# H05R0.net
KiCad netlist of a schematic drawn in EAGLE
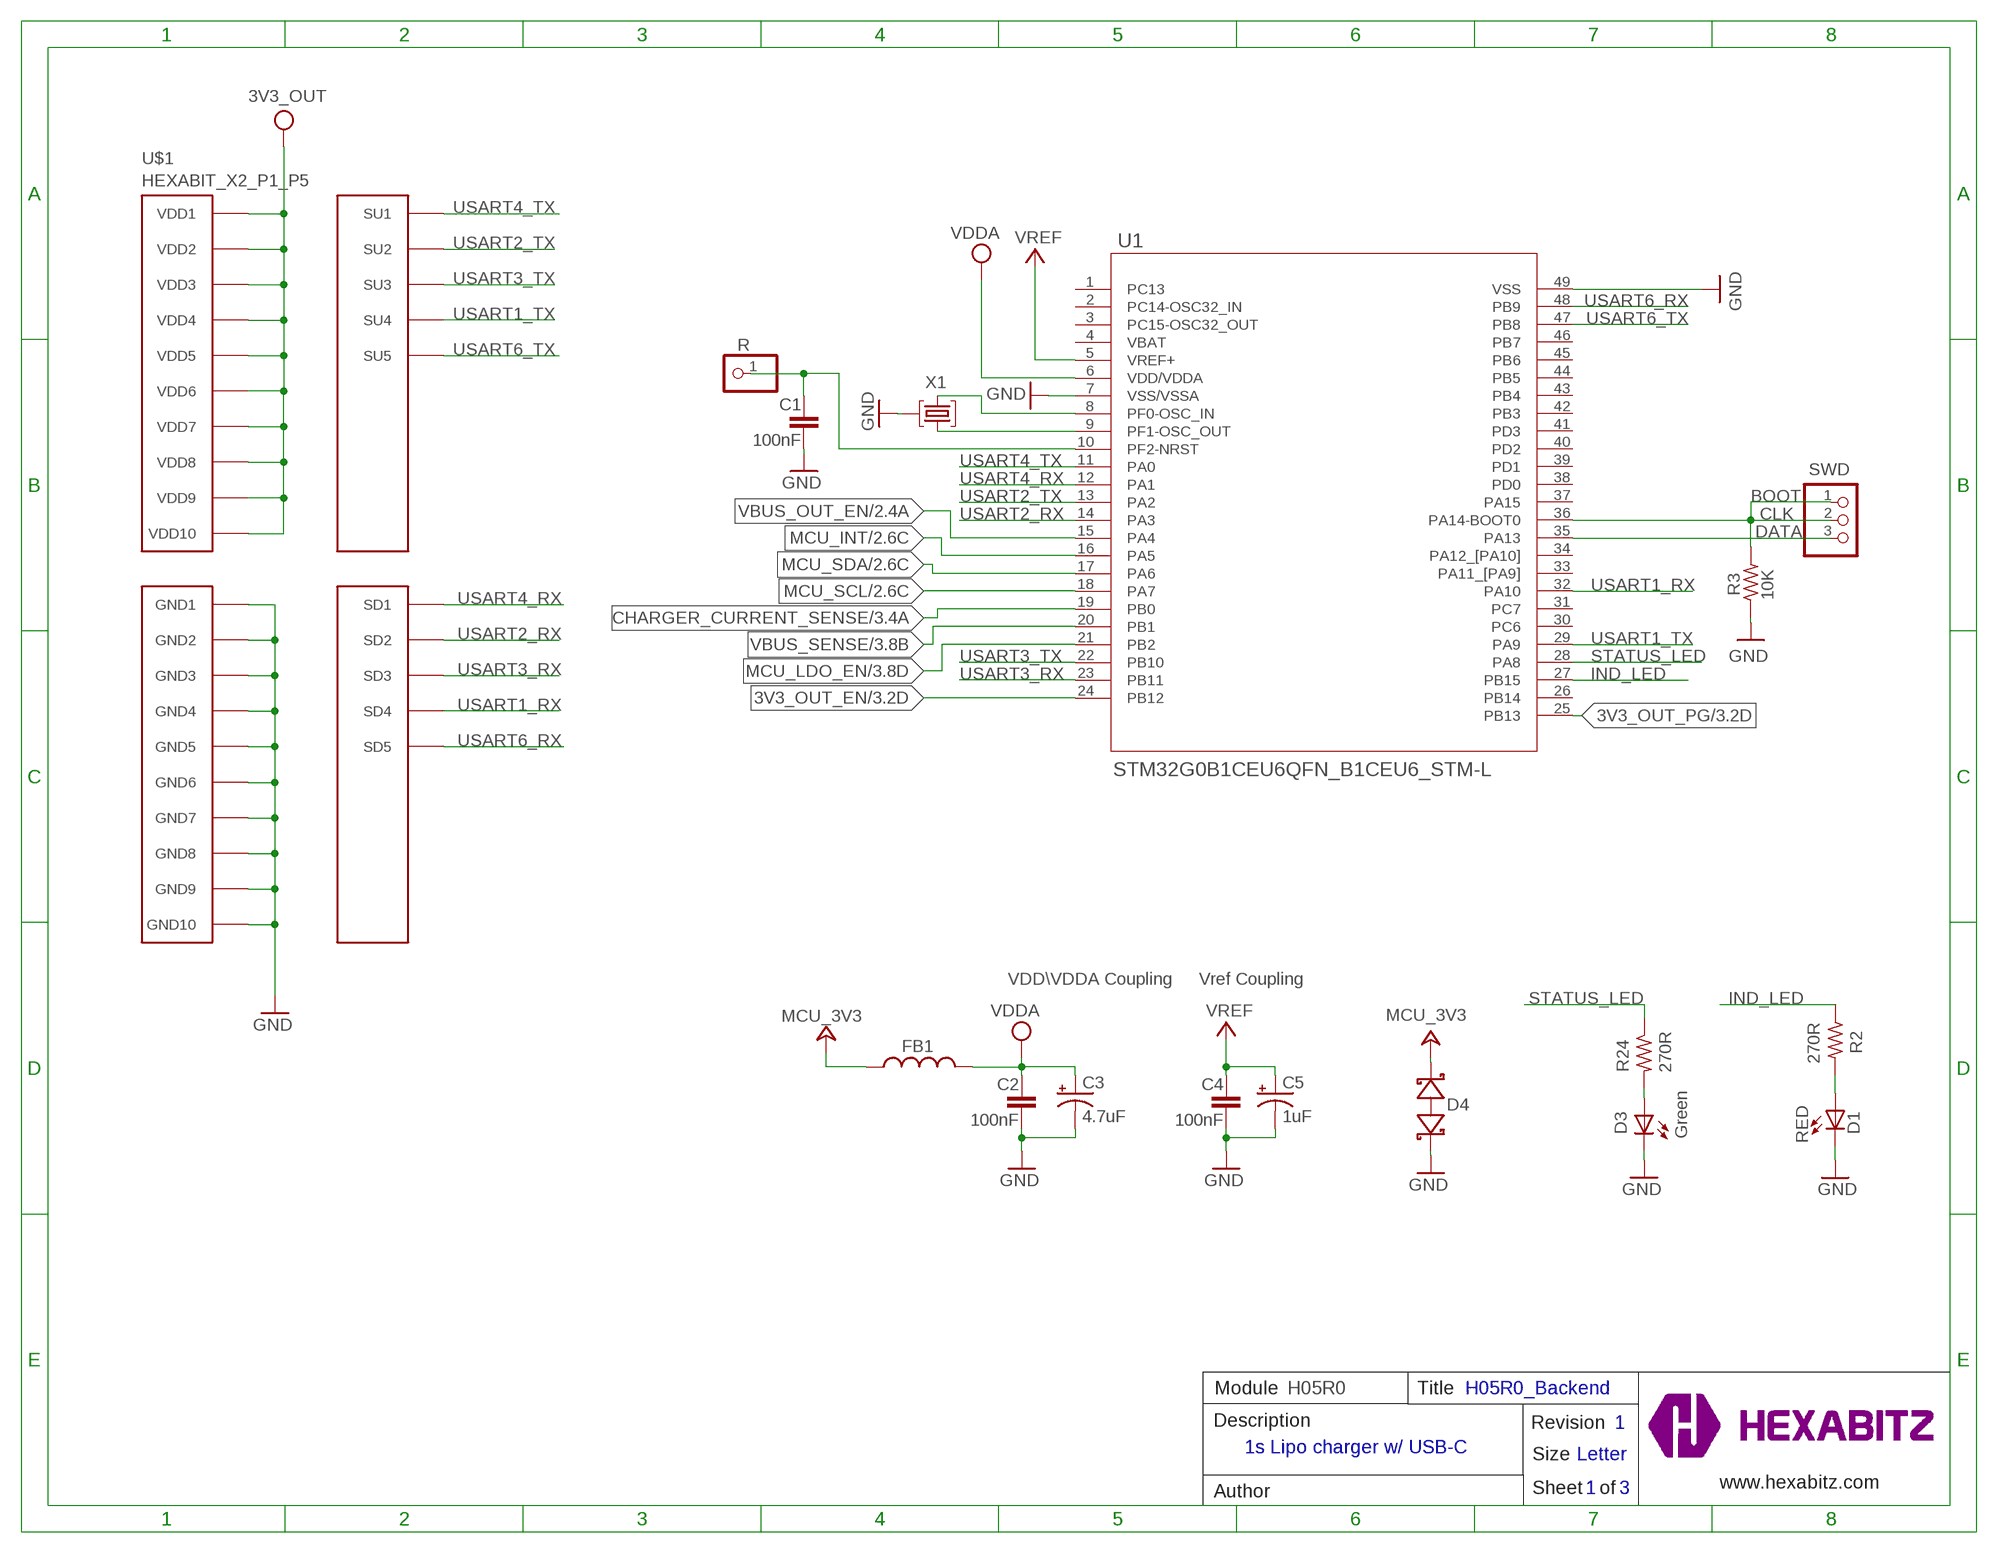
[diagram p0: schematic, sheet 1]
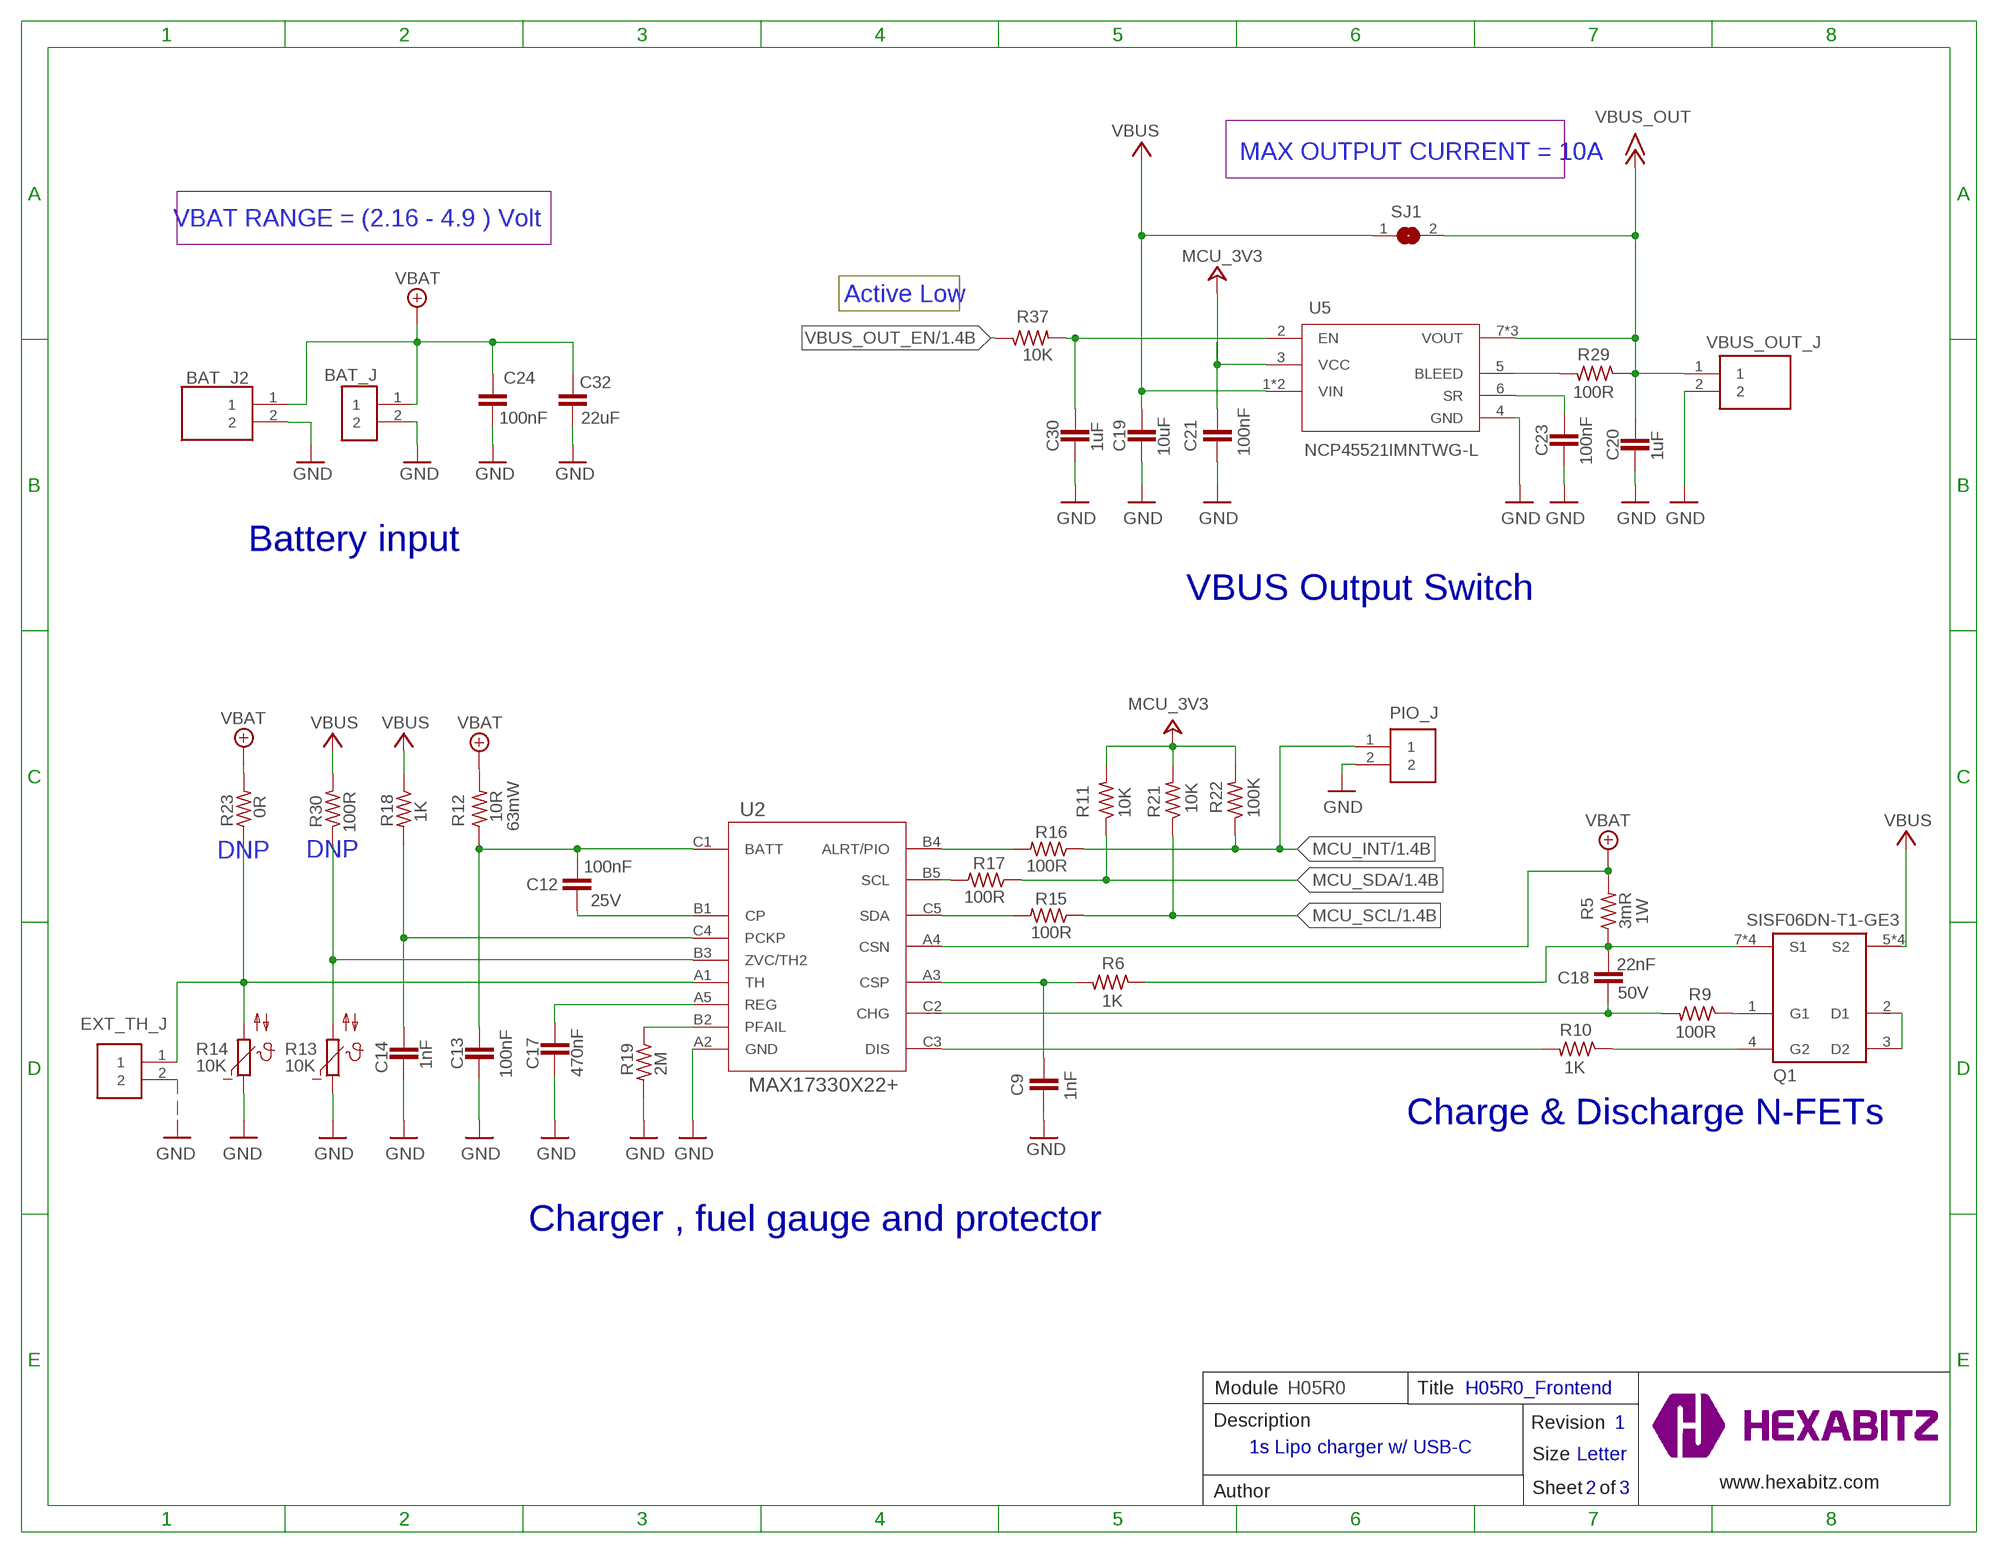
[diagram p1: schematic, sheet 2]
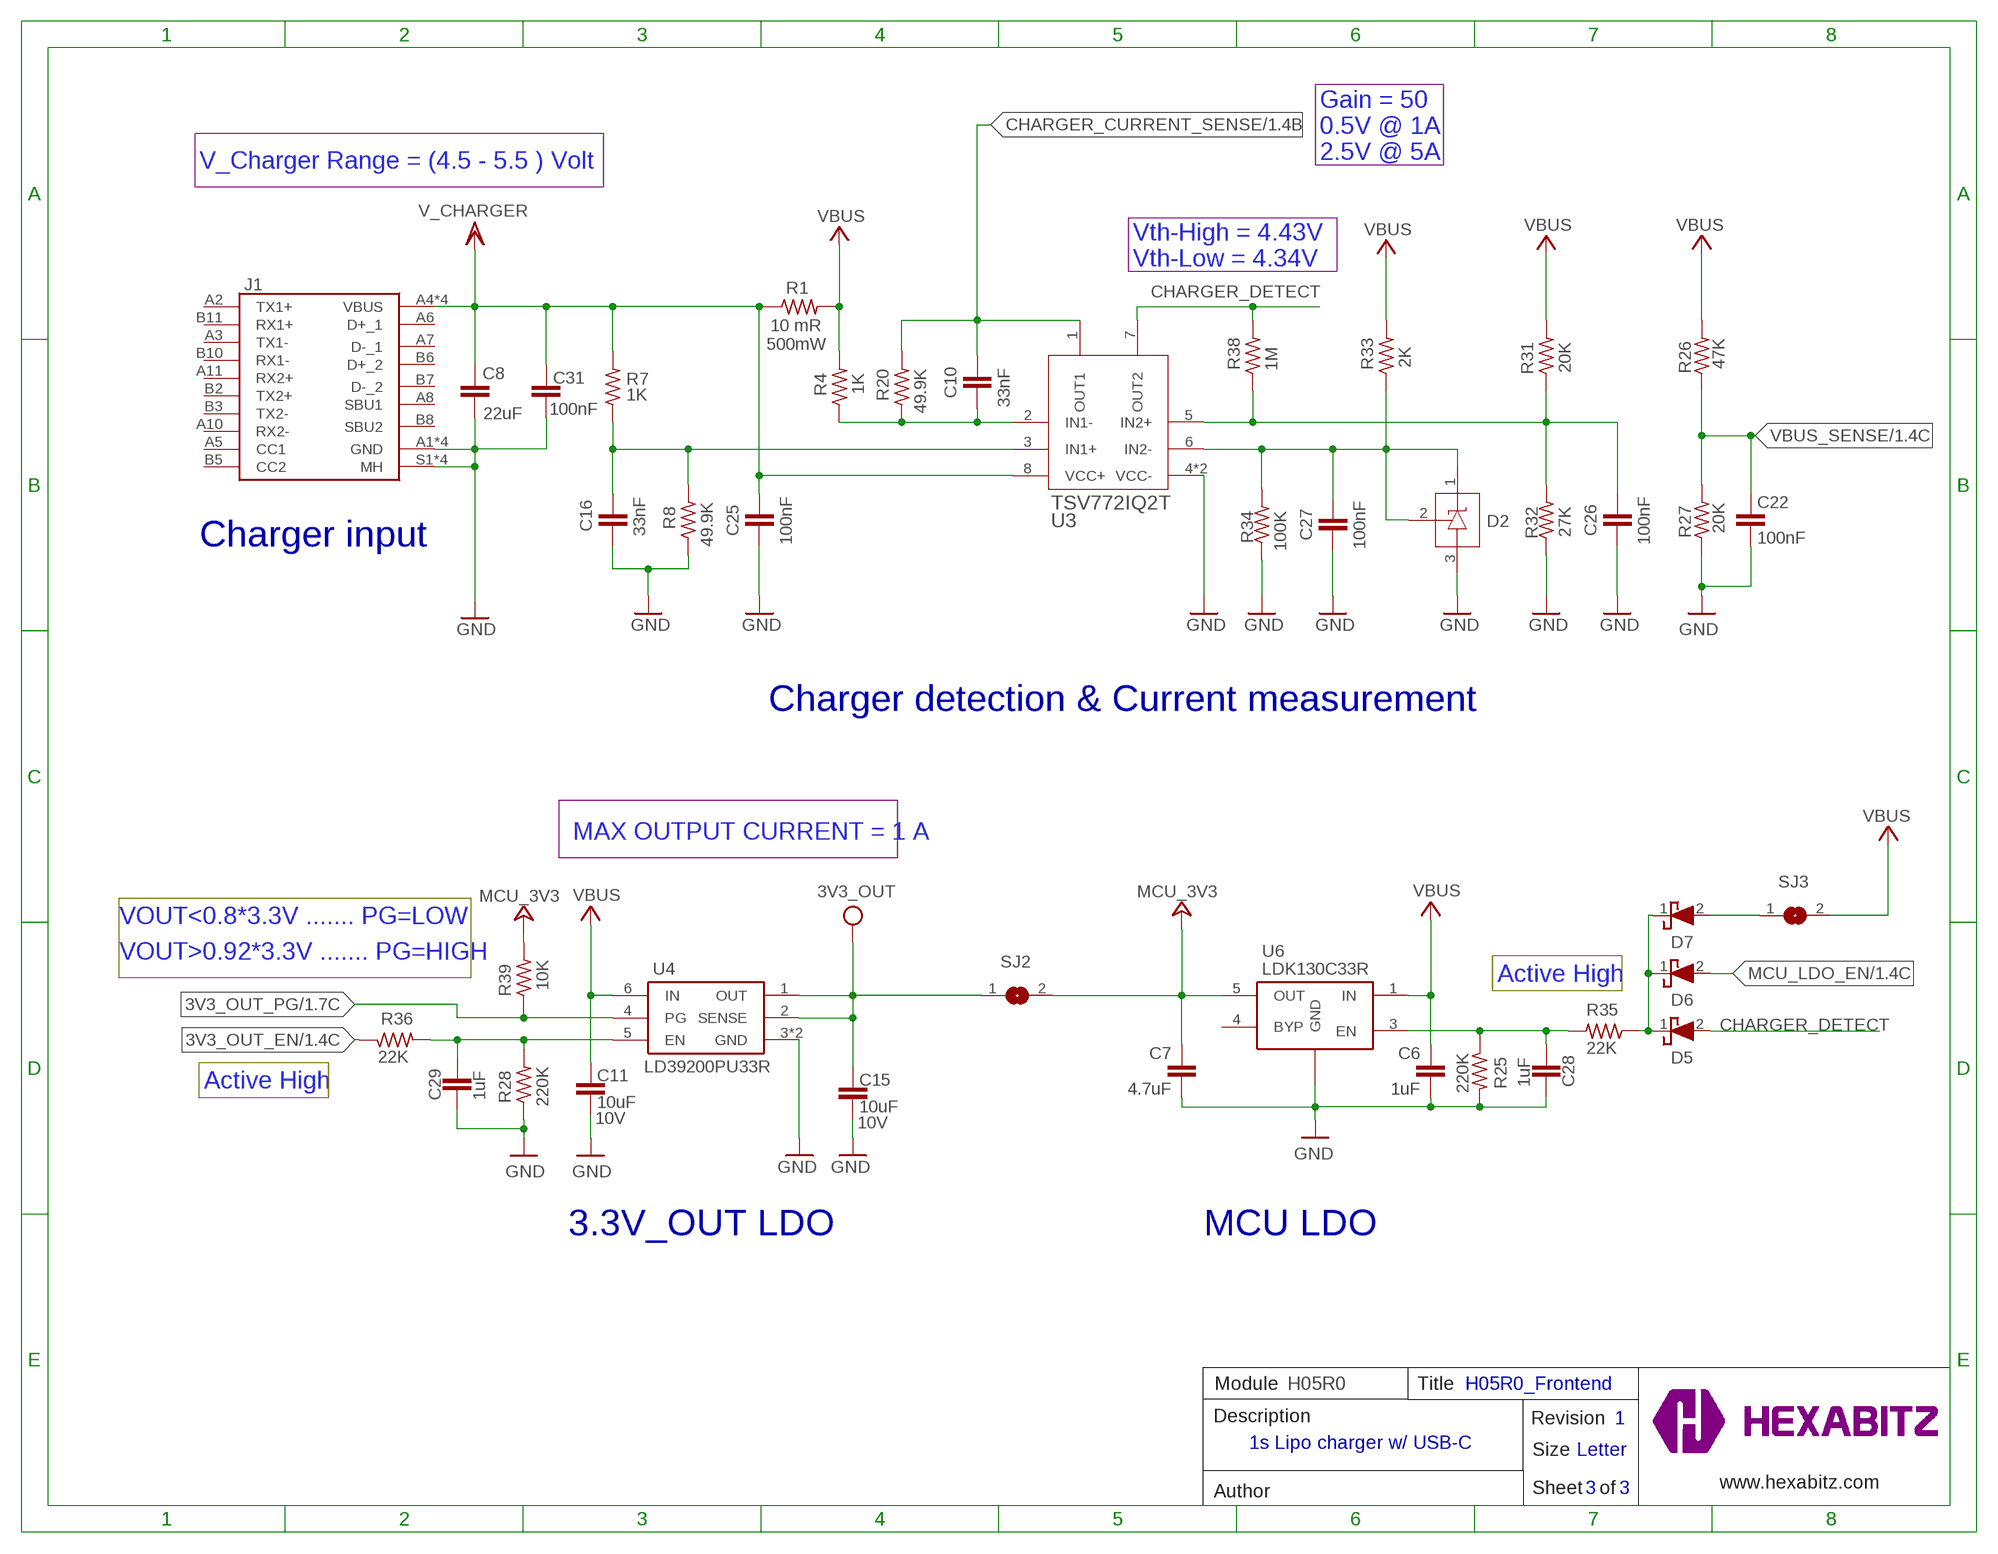
[diagram p2: schematic, sheet 3]

(export (version "E")
  (design (tool "Eeschema 10.0.6"))
  (components
    (comp (ref "C1")
      (value "100nF")
      (footprint "eagle-import:C-0603")
      (libsource (lib "eagle-import") (part "C-0603"))
    )
    (comp (ref "C2")
      (value "100nF")
      (footprint "eagle-import:C-0603")
      (libsource (lib "eagle-import") (part "C-0603"))
    )
    (comp (ref "C3")
      (value "4.7uF")
      (footprint "eagle-import:C-0805-POL")
      (libsource (lib "eagle-import") (part "C-0805-POL"))
    )
    (comp (ref "C4")
      (value "100nF")
      (footprint "eagle-import:C-0603")
      (libsource (lib "eagle-import") (part "C-0603"))
    )
    (comp (ref "C5")
      (value "1uF")
      (footprint "eagle-import:C-0805-POL")
      (libsource (lib "eagle-import") (part "C-0805-POL"))
    )
    (comp (ref "D1")
      (value "RED")
      (footprint "eagle-import:VLMS1300-GS08")
      (fields
        (field (name "MPN") "VLMS1300-GS08")
        (field (name "MFN") "Vishay")
        (field (name "MPN_1") "VLMS1300-GS08")
        (field (name "OCTOPART_URL") "https://octopart.com/vlms1300-gs08-vishay-21709201?r=sp&s=_gcP4_q8T1SC6PJQPTQ9yA")
      )
      (libsource (lib "eagle-import") (part "VLMS1300-GS08"))
    )
    (comp (ref "D3")
      (value "Green")
      (footprint "eagle-import:VLMTG1300-GS08")
      (fields
        (field (name "MPN") "VLMTG1300-GS08")
        (field (name "MFN") "Vishay")
        (field (name "MPN_1") "VLMS1300-GS08")
        (field (name "OCTOPART_URL") "https://octopart.com/vlms1300-gs08-vishay-21709201?r=sp&s=_gcP4_q8T1SC6PJQPTQ9yA")
      )
      (libsource (lib "eagle-import") (part "VLMTG1300-GS08"))
    )
    (comp (ref "D4")
      (value "BOURNS_CDSOD323-T03SCBOURNS_CDSOD323-T03SC_0_0")
      (footprint "eagle-import:BOURNS_CDSOD323-T03SC_0")
      (fields (field (name "MPN") "CDSOD323-T03SC"))
      (libsource (lib "eagle-import") (part "BOURNS_CDSOD323-T03SCBOURNS_CDSOD323-T03SC_0_0"))
    )
    (comp (ref "FB1")
      (value "FB-0603")
      (footprint "eagle-import:FB-0603")
      (libsource (lib "eagle-import") (part "FB-0603"))
    )
    (comp (ref "R")
      (value "R")
      (footprint "eagle-import:1X01")
      (fields (field (name "MPN") "87227-1"))
      (libsource (lib "eagle-import") (part "PINHD-1X1"))
    )
    (comp (ref "R2")
      (value "270R")
      (footprint "eagle-import:R-0603")
      (libsource (lib "eagle-import") (part "R-0603"))
    )
    (comp (ref "R3")
      (value "10K")
      (footprint "eagle-import:R-0603")
      (libsource (lib "eagle-import") (part "R-0603"))
    )
    (comp (ref "R24")
      (value "270R")
      (footprint "eagle-import:R-0603")
      (libsource (lib "eagle-import") (part "R-0603"))
    )
    (comp (ref "SWD")
      (value "PINHD-1X3")
      (footprint "eagle-import:1X03")
      (libsource (lib "eagle-import") (part "PINHD-1X3"))
    )
    (comp (ref "TRIMBLE-LOGO1")
      (value "HEXA-LOGO")
      (footprint "eagle-import:HEXA-LOGO")
      (libsource (lib "eagle-import") (part "HEXA-LOGO"))
    )
    (comp (ref "U$1")
      (value "HEXABIT_X2_P1_P5")
      (footprint "eagle-import:HEXABIT_17.32_X2_P1_P5")
      (libsource (lib "eagle-import") (part "HEXABIT_X2_P1_P5"))
    )
    (comp (ref "U1")
      (value "STM32G0B1CEU6QFN_B1CEU6_STM-L")
      (footprint "eagle-import:QFN_B1CEU6_STM-L")
      (fields
        (field (name "MANUFACTURER_PART_NUMBER") "STM32G0B1CEU6")
        (field (name "COPYRIGHT") "Copyright (C) 2021 Ultra Librarian. All rights reserved.")
      )
      (libsource (lib "eagle-import") (part "STM32G0B1CEU6QFN_B1CEU6_STM-L"))
    )
    (comp (ref "X1")
      (value "XTALL_CSTCE8M00G52")
      (footprint "eagle-import:XTALL_CSTCE8M00G52")
      (fields (field (name "MPN") "CSTCE8M00G52Z-R0"))
      (libsource (lib "eagle-import") (part "XTALL_CSTCE8M00G52"))
    )
    (comp (ref "BAT_J")
      (value "B2B-PH-K-S(LF)(SN)")
      (footprint "eagle-import:JST_B2B-PH-K-S(LF)(SN)")
      (fields (field (name "MF") "JST Sales"))
      (libsource (lib "eagle-import") (part "B2B-PH-K-S(LF)(SN)"))
    )
    (comp (ref "BAT_J2")
      (value "B2P-VH-FB-B_LF__SN_")
      (footprint "eagle-import:B2PVHFBBLFSN")
      (fields (field (name "MANUFACTURER_PART_NUMBER") "B2P-VH-FB-B(LF)(SN)"))
      (libsource (lib "eagle-import") (part "B2P-VH-FB-B_LF__SN_"))
    )
    (comp (ref "C9")
      (value "1nF")
      (footprint "eagle-import:C-0603")
      (fields (field (name "VOLTAGE_RATING") "50V"))
      (libsource (lib "eagle-import") (part "C-0603"))
    )
    (comp (ref "C12")
      (value "100nF")
      (footprint "eagle-import:C-0603")
      (fields (field (name "VOLTAGE_RATING") "25V"))
      (libsource (lib "eagle-import") (part "C-0603"))
    )
    (comp (ref "C13")
      (value "100nF")
      (footprint "eagle-import:C-0603")
      (fields (field (name "VOLTAGE_RATING") "10V"))
      (libsource (lib "eagle-import") (part "C-0603"))
    )
    (comp (ref "C14")
      (value "1nF")
      (footprint "eagle-import:C-0603")
      (fields (field (name "VOLTAGE_RATING") "50V"))
      (libsource (lib "eagle-import") (part "C-0603"))
    )
    (comp (ref "C17")
      (value "470nF")
      (footprint "eagle-import:C-0603")
      (fields (field (name "VOLTAGE_RATING") "10V"))
      (libsource (lib "eagle-import") (part "C-0603"))
    )
    (comp (ref "C18")
      (value "22nF")
      (footprint "eagle-import:C-0603")
      (fields (field (name "VOLTAGE_RATING") "50V"))
      (libsource (lib "eagle-import") (part "C-0603"))
    )
    (comp (ref "C19")
      (value "10uF")
      (footprint "eagle-import:C-0805")
      (libsource (lib "eagle-import") (part "C-0805"))
    )
    (comp (ref "C20")
      (value "1uF")
      (footprint "eagle-import:C-0805")
      (libsource (lib "eagle-import") (part "C-0805"))
    )
    (comp (ref "C21")
      (value "100nF")
      (footprint "eagle-import:C-0603")
      (fields (field (name "MPN") "GRM187R61A226ME15") (field (name "VOLTAGE_RATING") "10V"))
      (libsource (lib "eagle-import") (part "C-0603"))
    )
    (comp (ref "C23")
      (value "100nF")
      (footprint "eagle-import:C-0603")
      (fields (field (name "MPN") "GRM187R61A226ME15") (field (name "VOLTAGE_RATING") "10V"))
      (libsource (lib "eagle-import") (part "C-0603"))
    )
    (comp (ref "C24")
      (value "100nF")
      (footprint "eagle-import:C-0603")
      (fields (field (name "VOLTAGE_RATING") "50V"))
      (libsource (lib "eagle-import") (part "C-0603"))
    )
    (comp (ref "C30")
      (value "1uF")
      (footprint "eagle-import:C-0805")
      (fields (field (name "MPN") "GRM187R61A226ME15") (field (name "VOLTAGE_RATING") "10V"))
      (libsource (lib "eagle-import") (part "C-0805"))
    )
    (comp (ref "C32")
      (value "22uF")
      (footprint "eagle-import:C-0805")
      (libsource (lib "eagle-import") (part "C-0805"))
    )
    (comp (ref "EXT_TH_J")
      (value "3-644456-2")
      (footprint "eagle-import:TE_3-644456-2")
      (fields (field (name "MF") "TE Connectivity") (field (name "MPN") "87224-1"))
      (libsource (lib "eagle-import") (part "3-644456-2"))
    )
    (comp (ref "PIO_J")
      (value "3-644456-2")
      (footprint "eagle-import:TE_3-644456-2")
      (fields (field (name "MF") "TE Connectivity") (field (name "MPN") "87224-1"))
      (libsource (lib "eagle-import") (part "3-644456-2"))
    )
    (comp (ref "Q1")
      (value "SISF06DN-T1-GE3")
      (footprint "eagle-import:SISF06DNT1GE3")
      (fields (field (name "MOUSER_PART_NUMBER") "78-SISF06DN-T1-GE3"))
      (libsource (lib "eagle-import") (part "SISF06DN-T1-GE3"))
    )
    (comp (ref "R5")
      (value "3mR")
      (footprint "eagle-import:R1206")
      (fields
        (field (name "MPN") "RNCF2512BTE1M10")
        (field (name "MPN_1") "WFC12063L000FE66")
        (field (name "OCTOPART_URL") "https://www.digikey.com/en/products/detail/vishay-dale/WFC12063L000FE66/15908406")
        (field (name "POWER") "1W")
      )
      (libsource (lib "eagle-import") (part "R_1206R1206"))
    )
    (comp (ref "R6")
      (value "1K")
      (footprint "eagle-import:R-0603")
      (libsource (lib "eagle-import") (part "R-0603"))
    )
    (comp (ref "R9")
      (value "100R")
      (footprint "eagle-import:R-0603")
      (libsource (lib "eagle-import") (part "R-0603"))
    )
    (comp (ref "R10")
      (value "1K")
      (footprint "eagle-import:R-0603")
      (libsource (lib "eagle-import") (part "R-0603"))
    )
    (comp (ref "R11")
      (value "10K")
      (footprint "eagle-import:R-0603")
      (libsource (lib "eagle-import") (part "R-0603"))
    )
    (comp (ref "R12")
      (value "10R")
      (footprint "eagle-import:R-0603")
      (fields (field (name "POWER") "63mW"))
      (libsource (lib "eagle-import") (part "R-0603"))
    )
    (comp (ref "R13")
      (value "10K")
      (footprint "eagle-import:R-0603")
      (fields (field (name "MPN") "NCP18XH103F03RB"))
      (libsource (lib "eagle-import") (part "NCP18XH103F03RBNCP18XH103F03RB"))
    )
    (comp (ref "R14")
      (value "10K")
      (footprint "eagle-import:R-0603")
      (fields (field (name "MPN") "NCP18XH103F03RB"))
      (libsource (lib "eagle-import") (part "NCP18XH103F03RBNCP18XH103F03RB"))
    )
    (comp (ref "R15")
      (value "100R")
      (footprint "eagle-import:R-0603")
      (libsource (lib "eagle-import") (part "R-0603"))
    )
    (comp (ref "R16")
      (value "100R")
      (footprint "eagle-import:R-0603")
      (libsource (lib "eagle-import") (part "R-0603"))
    )
    (comp (ref "R17")
      (value "100R")
      (footprint "eagle-import:R-0603")
      (libsource (lib "eagle-import") (part "R-0603"))
    )
    (comp (ref "R18")
      (value "1K")
      (footprint "eagle-import:R-0603")
      (libsource (lib "eagle-import") (part "R-0603"))
    )
    (comp (ref "R19")
      (value "2M")
      (footprint "eagle-import:R-0603")
      (libsource (lib "eagle-import") (part "R-0603"))
    )
    (comp (ref "R21")
      (value "10K")
      (footprint "eagle-import:R-0603")
      (libsource (lib "eagle-import") (part "R-0603"))
    )
    (comp (ref "R22")
      (value "100K")
      (footprint "eagle-import:R-0603")
      (libsource (lib "eagle-import") (part "R-0603"))
    )
    (comp (ref "R23")
      (value "DNP")
      (footprint "eagle-import:R-0603")
      (fields (field (name "RESISTANCE") "0R") (field (name "STATE") "DNP"))
      (libsource (lib "eagle-import") (part "R-0603"))
    )
    (comp (ref "R29")
      (value "100R")
      (footprint "eagle-import:R-0603")
      (libsource (lib "eagle-import") (part "R-0603"))
    )
    (comp (ref "R30")
      (value "100R")
      (footprint "eagle-import:R-0603")
      (fields (field (name "STATE") "DNP"))
      (libsource (lib "eagle-import") (part "R-0603"))
    )
    (comp (ref "R37")
      (value "10K")
      (footprint "eagle-import:R-0603")
      (libsource (lib "eagle-import") (part "R-0603"))
    )
    (comp (ref "SJ1") (value "SJ") (footprint "eagle-import:SJ") (libsource (lib "eagle-import") (part "SJ")))
    (comp (ref "U2")
      (value "MAX17330X22+")
      (footprint "eagle-import:21-100433_W151J2+1_MXM")
      (fields (field (name "COPYRIGHT") "Copyright (C) 2023 Ultra Librarian. All rights reserved."))
      (libsource (lib "eagle-import") (part "MAX17330X22+21-100433_W151J2+1_MXM"))
    )
    (comp (ref "U5")
      (value "NCP45521IMNTWG-L")
      (footprint "eagle-import:DFN8_2X2_ONS")
      (fields (field (name "COPYRIGHT") "Copyright (C) 2024 Ultra Librarian. All rights reserved."))
      (libsource (lib "eagle-import") (part "NCP45521IMNTWG-LDFN8_2X2_ONS"))
    )
    (comp (ref "VBUS_OUT_J")
      (value "1984617")
      (footprint "eagle-import:1984617")
      (fields (field (name "MOUSER_PART_NUMBER") "651-1984617"))
      (libsource (lib "eagle-import") (part "1984617"))
    )
    (comp (ref "C6")
      (value "1uF")
      (footprint "eagle-import:C-0805")
      (libsource (lib "eagle-import") (part "C-0805"))
    )
    (comp (ref "C7")
      (value "4.7uF")
      (footprint "eagle-import:C-0805")
      (libsource (lib "eagle-import") (part "C-0805"))
    )
    (comp (ref "C8")
      (value "22uF")
      (footprint "eagle-import:C-0805")
      (libsource (lib "eagle-import") (part "C-0805"))
    )
    (comp (ref "C10")
      (value "33nF")
      (footprint "eagle-import:C-0603")
      (fields (field (name "VOLTAGE_RATING") "50V"))
      (libsource (lib "eagle-import") (part "C-0603"))
    )
    (comp (ref "C11")
      (value "10uF")
      (footprint "eagle-import:C-0805")
      (fields (field (name "MPN") "GRM187R61A226ME15") (field (name "VOLTAGE_RATING") "10V"))
      (libsource (lib "eagle-import") (part "C-0805"))
    )
    (comp (ref "C15")
      (value "10uF")
      (footprint "eagle-import:C-0805")
      (fields (field (name "MPN") "GRM187R61A226ME15") (field (name "VOLTAGE_RATING") "10V"))
      (libsource (lib "eagle-import") (part "C-0805"))
    )
    (comp (ref "C16")
      (value "33nF")
      (footprint "eagle-import:C-0603")
      (fields (field (name "VOLTAGE_RATING") "50V"))
      (libsource (lib "eagle-import") (part "C-0603"))
    )
    (comp (ref "C22")
      (value "100nF")
      (footprint "eagle-import:C-0603")
      (fields (field (name "VOLTAGE_RATING") "50V"))
      (libsource (lib "eagle-import") (part "C-0603"))
    )
    (comp (ref "C25")
      (value "100nF")
      (footprint "eagle-import:C-0603")
      (fields (field (name "VOLTAGE_RATING") "50V"))
      (libsource (lib "eagle-import") (part "C-0603"))
    )
    (comp (ref "C26")
      (value "100nF")
      (footprint "eagle-import:C-0603")
      (fields (field (name "VOLTAGE_RATING") "50V"))
      (libsource (lib "eagle-import") (part "C-0603"))
    )
    (comp (ref "C27")
      (value "100nF")
      (footprint "eagle-import:C-0603")
      (fields (field (name "VOLTAGE_RATING") "50V"))
      (libsource (lib "eagle-import") (part "C-0603"))
    )
    (comp (ref "C28")
      (value "1uF")
      (footprint "eagle-import:C-0805")
      (fields (field (name "MPN") "GRM187R61A226ME15") (field (name "VOLTAGE_RATING") "10V"))
      (libsource (lib "eagle-import") (part "C-0805"))
    )
    (comp (ref "C29")
      (value "1uF")
      (footprint "eagle-import:C-0805")
      (fields (field (name "MPN") "GRM187R61A226ME15") (field (name "VOLTAGE_RATING") "10V"))
      (libsource (lib "eagle-import") (part "C-0805"))
    )
    (comp (ref "C31")
      (value "100nF")
      (footprint "eagle-import:C-0603")
      (fields (field (name "VOLTAGE_RATING") "50V"))
      (libsource (lib "eagle-import") (part "C-0603"))
    )
    (comp (ref "D2")
      (value "TL431QDBZR,215")
      (footprint "eagle-import:SOT23_TO-236AB_NEX")
      (fields
        (field (name "MANUFACTURER_PART_NUMBER") "TS2431BILT")
        (field (name "COPYRIGHT") "Copyright (C) 2022 Ultra Librarian. All rights reserved.")
      )
      (libsource (lib "eagle-import") (part "TL431QDBZR,215"))
    )
    (comp (ref "D5")
      (value "CUS10S30,H3F")
      (footprint "eagle-import:1SS357TPH3F")
      (fields (field (name "MOUSER_PART_NUMBER") "757-CUS10S30H3F"))
      (libsource (lib "eagle-import") (part "CUS10S30,H3F"))
    )
    (comp (ref "D6")
      (value "CUS10S30,H3F")
      (footprint "eagle-import:1SS357TPH3F")
      (fields (field (name "MOUSER_PART_NUMBER") "757-CUS10S30H3F"))
      (libsource (lib "eagle-import") (part "CUS10S30,H3F"))
    )
    (comp (ref "D7")
      (value "CUS10S30,H3F")
      (footprint "eagle-import:1SS357TPH3F")
      (fields (field (name "MOUSER_PART_NUMBER") "757-CUS10S30H3F"))
      (libsource (lib "eagle-import") (part "CUS10S30,H3F"))
    )
    (comp (ref "J1")
      (value "12401610E4#2A12401610E42A")
      (footprint "eagle-import:AMPHENOL_12401610E4_2A")
      (libsource (lib "eagle-import") (part "12401610E4#2A12401610E42A"))
    )
    (comp (ref "R1")
      (value "10 mR")
      (footprint "eagle-import:R-0805")
      (fields (field (name "POWR") "500mW"))
      (libsource (lib "eagle-import") (part "R-0805"))
    )
    (comp (ref "R4")
      (value "1K")
      (footprint "eagle-import:R-0603")
      (fields (field (name "STATE") "DNP"))
      (libsource (lib "eagle-import") (part "R-0603"))
    )
    (comp (ref "R7")
      (value "1K")
      (footprint "eagle-import:R-0603")
      (fields (field (name "STATE") "DNP"))
      (libsource (lib "eagle-import") (part "R-0603"))
    )
    (comp (ref "R8")
      (value "49.9K")
      (footprint "eagle-import:R-0603")
      (fields (field (name "STATE") "DNP"))
      (libsource (lib "eagle-import") (part "R-0603"))
    )
    (comp (ref "R20")
      (value "49.9K")
      (footprint "eagle-import:R-0603")
      (fields (field (name "STATE") "DNP"))
      (libsource (lib "eagle-import") (part "R-0603"))
    )
    (comp (ref "R25")
      (value "220K")
      (footprint "eagle-import:R-0603")
      (libsource (lib "eagle-import") (part "R-0603"))
    )
    (comp (ref "R26")
      (value "47K")
      (footprint "eagle-import:R-0603")
      (libsource (lib "eagle-import") (part "R-0603"))
    )
    (comp (ref "R27")
      (value "20K")
      (footprint "eagle-import:R-0603")
      (libsource (lib "eagle-import") (part "R-0603"))
    )
    (comp (ref "R28")
      (value "220K")
      (footprint "eagle-import:R-0603")
      (fields (field (name "TOLERANCE") "1%"))
      (libsource (lib "eagle-import") (part "R-0603"))
    )
    (comp (ref "R31")
      (value "20K")
      (footprint "eagle-import:R-0603")
      (fields (field (name "STATE") "DNP"))
      (libsource (lib "eagle-import") (part "R-0603"))
    )
    (comp (ref "R32")
      (value "27K")
      (footprint "eagle-import:R-0603")
      (fields (field (name "STATE") "DNP"))
      (libsource (lib "eagle-import") (part "R-0603"))
    )
    (comp (ref "R33")
      (value "2K")
      (footprint "eagle-import:R-0603")
      (fields (field (name "STATE") "DNP"))
      (libsource (lib "eagle-import") (part "R-0603"))
    )
    (comp (ref "R34")
      (value "100K")
      (footprint "eagle-import:R-0603")
      (fields (field (name "STATE") "DNP"))
      (libsource (lib "eagle-import") (part "R-0603"))
    )
    (comp (ref "R35")
      (value "22K")
      (footprint "eagle-import:R-0603")
      (libsource (lib "eagle-import") (part "R-0603"))
    )
    (comp (ref "R36")
      (value "22K")
      (footprint "eagle-import:R-0603")
      (libsource (lib "eagle-import") (part "R-0603"))
    )
    (comp (ref "R38")
      (value "1M")
      (footprint "eagle-import:R-0603")
      (fields (field (name "STATE") "DNP"))
      (libsource (lib "eagle-import") (part "R-0603"))
    )
    (comp (ref "R39")
      (value "10K")
      (footprint "eagle-import:R-0603")
      (fields (field (name "TOLERANCE") "1%"))
      (libsource (lib "eagle-import") (part "R-0603"))
    )
    (comp (ref "SJ2") (value "SJ") (footprint "eagle-import:SJ") (libsource (lib "eagle-import") (part "SJ")))
    (comp (ref "SJ3") (value "SJ") (footprint "eagle-import:SJ") (libsource (lib "eagle-import") (part "SJ")))
    (comp (ref "U3")
      (value "TSV772IQ2T")
      (footprint "eagle-import:SON50P200X200X60-9N")
      (fields (field (name "MOUSER_PART_NUMBER") "511-TSV772IQ2T"))
      (libsource (lib "eagle-import") (part "TSV772IQ2T"))
    )
    (comp (ref "U4")
      (value "LD39200PU33R")
      (footprint "eagle-import:SON95P300X300X100-7N")
      (fields (field (name "MOUSER_PART_NUMBER") "511-LD39200PU33R"))
      (libsource (lib "eagle-import") (part "LD39200PU33R"))
    )
    (comp (ref "U6")
      (value "LDK130C33R")
      (footprint "eagle-import:SOT65P210X110-5N")
      (fields (field (name "MOUSER_PART_NUMBER") "511-LDK130C33R"))
      (libsource (lib "eagle-import") (part "LDK130C33R"))
    )
  )
  (nets
    (net (code "1") (name "3V3_OUT") (class "Default")
      (node (ref "C15") (pin "2") (pinfunction "2_2") (pintype "passive"))
      (node (ref "SJ2") (pin "1") (pinfunction "1_1") (pintype "passive"))
      (node (ref "U$1") (pin "PAD_PU11") (pinfunction "VDD1_PAD_PU11") (pintype "power_in"))
      (node (ref "U$1") (pin "PAD_PU12") (pinfunction "VDD2_PAD_PU12") (pintype "power_in"))
      (node (ref "U$1") (pin "PAD_PU13") (pinfunction "VDD3_PAD_PU13") (pintype "power_in"))
      (node (ref "U$1") (pin "PAD_PU14") (pinfunction "VDD4_PAD_PU14") (pintype "power_in"))
      (node (ref "U$1") (pin "PAD_PU15") (pinfunction "VDD5_PAD_PU15") (pintype "power_in"))
      (node (ref "U$1") (pin "PAD_PU16") (pinfunction "VDD6_PAD_PU16") (pintype "power_in"))
      (node (ref "U$1") (pin "PAD_PU17") (pinfunction "VDD7_PAD_PU17") (pintype "power_in"))
      (node (ref "U$1") (pin "PAD_PU18") (pinfunction "VDD8_PAD_PU18") (pintype "power_in"))
      (node (ref "U$1") (pin "PAD_PU19") (pinfunction "VDD9_PAD_PU19") (pintype "power_in"))
      (node (ref "U$1") (pin "PAD_PU20") (pinfunction "VDD10_PAD_PU20") (pintype "power_in"))
      (node (ref "U4") (pin "1") (pinfunction "OUT_1") (pintype "bidirectional"))
      (node (ref "U4") (pin "2") (pinfunction "SENSE_2") (pintype "bidirectional"))
    )
    (net (code "2") (name "3V3_OUT_EN") (class "Default")
      (node (ref "R36") (pin "1") (pinfunction "1_1") (pintype "passive"))
      (node (ref "U1") (pin "24") (pinfunction "PB12_24") (pintype "bidirectional"))
    )
    (net (code "3") (name "3V3_OUT_PG") (class "Default")
      (node (ref "R39") (pin "1") (pinfunction "1_1") (pintype "passive"))
      (node (ref "U1") (pin "25") (pinfunction "PB13_25") (pintype "bidirectional"))
      (node (ref "U4") (pin "4") (pinfunction "PG_4") (pintype "bidirectional"))
    )
    (net (code "4") (name "CHARGER_CURRENT_SENSE") (class "Default")
      (node (ref "C10") (pin "2") (pinfunction "2_2") (pintype "passive"))
      (node (ref "R20") (pin "2") (pinfunction "2_2") (pintype "passive"))
      (node (ref "U1") (pin "19") (pinfunction "PB0_19") (pintype "bidirectional"))
      (node (ref "U3") (pin "1") (pinfunction "OUT1_1") (pintype "output"))
    )
    (net (code "5") (name "CHARGER_DETECT") (class "Default")
      (node (ref "D5") (pin "2") (pinfunction "A_2") (pintype "bidirectional"))
      (node (ref "R38") (pin "2") (pinfunction "2_2") (pintype "passive"))
      (node (ref "U3") (pin "7") (pinfunction "OUT2_7") (pintype "output"))
    )
    (net (code "6") (name "CLK") (class "Default")
      (node (ref "R3") (pin "2") (pinfunction "2_2") (pintype "passive"))
      (node (ref "SWD") (pin "1") (pinfunction "1_1") (pintype "passive"))
      (node (ref "SWD") (pin "2") (pinfunction "2_2") (pintype "passive"))
      (node (ref "U1") (pin "36") (pinfunction "PA14-BOOT0_36") (pintype "bidirectional"))
    )
    (net (code "7") (name "DATA") (class "Default")
      (node (ref "SWD") (pin "3") (pinfunction "3_3") (pintype "passive"))
      (node (ref "U1") (pin "35") (pinfunction "PA13_35") (pintype "bidirectional"))
    )
    (net (code "8") (name "GND") (class "Default")
      (node (ref "BAT_J") (pin "2") (pinfunction "2_2") (pintype "passive"))
      (node (ref "BAT_J2") (pin "2") (pinfunction "2_2") (pintype "bidirectional"))
      (node (ref "C1") (pin "2") (pinfunction "2_2") (pintype "passive"))
      (node (ref "C11") (pin "1") (pinfunction "1_1") (pintype "passive"))
      (node (ref "C13") (pin "2") (pinfunction "2_2") (pintype "passive"))
      (node (ref "C14") (pin "2") (pinfunction "2_2") (pintype "passive"))
      (node (ref "C15") (pin "1") (pinfunction "1_1") (pintype "passive"))
      (node (ref "C16") (pin "1") (pinfunction "1_1") (pintype "passive"))
      (node (ref "C17") (pin "1") (pinfunction "1_1") (pintype "passive"))
      (node (ref "C19") (pin "2") (pinfunction "2_2") (pintype "passive"))
      (node (ref "C2") (pin "2") (pinfunction "2_2") (pintype "passive"))
      (node (ref "C20") (pin "2") (pinfunction "2_2") (pintype "passive"))
      (node (ref "C21") (pin "1") (pinfunction "1_1") (pintype "passive"))
      (node (ref "C22") (pin "2") (pinfunction "2_2") (pintype "passive"))
      (node (ref "C23") (pin "1") (pinfunction "1_1") (pintype "passive"))
      (node (ref "C24") (pin "1") (pinfunction "1_1") (pintype "passive"))
      (node (ref "C25") (pin "1") (pinfunction "1_1") (pintype "passive"))
      (node (ref "C26") (pin "1") (pinfunction "1_1") (pintype "passive"))
      (node (ref "C27") (pin "1") (pinfunction "1_1") (pintype "passive"))
      (node (ref "C28") (pin "1") (pinfunction "1_1") (pintype "passive"))
      (node (ref "C29") (pin "1") (pinfunction "1_1") (pintype "passive"))
      (node (ref "C3") (pin "2") (pinfunction "-_2") (pintype "passive"))
      (node (ref "C30") (pin "1") (pinfunction "1_1") (pintype "passive"))
      (node (ref "C31") (pin "1") (pinfunction "1_1") (pintype "passive"))
      (node (ref "C32") (pin "2") (pinfunction "2_2") (pintype "passive"))
      (node (ref "C4") (pin "2") (pinfunction "2_2") (pintype "passive"))
      (node (ref "C5") (pin "2") (pinfunction "-_2") (pintype "passive"))
      (node (ref "C6") (pin "2") (pinfunction "2_2") (pintype "passive"))
      (node (ref "C7") (pin "2") (pinfunction "2_2") (pintype "passive"))
      (node (ref "C8") (pin "2") (pinfunction "2_2") (pintype "passive"))
      (node (ref "C9") (pin "1") (pinfunction "1_1") (pintype "passive"))
      (node (ref "D1") (pin "C") (pinfunction "C_C") (pintype "passive"))
      (node (ref "D2") (pin "3") (pinfunction "3_3") (pintype "passive"))
      (node (ref "D3") (pin "C") (pinfunction "C_C") (pintype "passive"))
      (node (ref "D4") (pin "1") (pinfunction "A_1") (pintype "passive"))
      (node (ref "EXT_TH_J") (pin "2") (pinfunction "2_2") (pintype "passive"))
      (node (ref "J1") (pin "A1") (pinfunction "GND_A1") (pintype "bidirectional"))
      (node (ref "J1") (pin "A12") (pinfunction "GND_A12") (pintype "bidirectional"))
      (node (ref "J1") (pin "B1") (pinfunction "GND_B1") (pintype "bidirectional"))
      (node (ref "J1") (pin "B12") (pinfunction "GND_B12") (pintype "bidirectional"))
      (node (ref "J1") (pin "S1") (pinfunction "MH_S1") (pintype "bidirectional"))
      (node (ref "J1") (pin "S2") (pinfunction "MH_S2") (pintype "bidirectional"))
      (node (ref "J1") (pin "S3") (pinfunction "MH_S3") (pintype "bidirectional"))
      (node (ref "J1") (pin "S4") (pinfunction "MH_S4") (pintype "bidirectional"))
      (node (ref "PIO_J") (pin "2") (pinfunction "2_2") (pintype "passive"))
      (node (ref "R13") (pin "1") (pinfunction "1_1") (pintype "passive"))
      (node (ref "R14") (pin "1") (pinfunction "1_1") (pintype "passive"))
      (node (ref "R19") (pin "2") (pinfunction "2_2") (pintype "passive"))
      (node (ref "R25") (pin "2") (pinfunction "2_2") (pintype "passive"))
      (node (ref "R27") (pin "1") (pinfunction "1_1") (pintype "passive"))
      (node (ref "R28") (pin "1") (pinfunction "1_1") (pintype "passive"))
      (node (ref "R3") (pin "1") (pinfunction "1_1") (pintype "passive"))
      (node (ref "R32") (pin "1") (pinfunction "1_1") (pintype "passive"))
      (node (ref "R34") (pin "1") (pinfunction "1_1") (pintype "passive"))
      (node (ref "R8") (pin "1") (pinfunction "1_1") (pintype "passive"))
      (node (ref "U$1") (pin "PAD_PD11") (pinfunction "GND1_PAD_PD11") (pintype "power_in"))
      (node (ref "U$1") (pin "PAD_PD12") (pinfunction "GND2_PAD_PD12") (pintype "power_in"))
      (node (ref "U$1") (pin "PAD_PD13") (pinfunction "GND3_PAD_PD13") (pintype "power_in"))
      (node (ref "U$1") (pin "PAD_PD14") (pinfunction "GND4_PAD_PD14") (pintype "power_in"))
      (node (ref "U$1") (pin "PAD_PD15") (pinfunction "GND5_PAD_PD15") (pintype "power_in"))
      (node (ref "U$1") (pin "PAD_PD16") (pinfunction "GND6_PAD_PD16") (pintype "power_in"))
      (node (ref "U$1") (pin "PAD_PD17") (pinfunction "GND7_PAD_PD17") (pintype "power_in"))
      (node (ref "U$1") (pin "PAD_PD18") (pinfunction "GND8_PAD_PD18") (pintype "power_in"))
      (node (ref "U$1") (pin "PAD_PD19") (pinfunction "GND9_PAD_PD19") (pintype "power_in"))
      (node (ref "U$1") (pin "PAD_PD20") (pinfunction "GND10_PAD_PD20") (pintype "power_in"))
      (node (ref "U1") (pin "49") (pinfunction "VSS_49") (pintype "passive"))
      (node (ref "U1") (pin "7") (pinfunction "VSS/VSSA_7") (pintype "passive"))
      (node (ref "U2") (pin "A2") (pinfunction "GND_A2") (pintype "passive"))
      (node (ref "U3") (pin "4") (pinfunction "VCC-_4") (pintype "power_in"))
      (node (ref "U3") (pin "9") (pinfunction "VCC-_9") (pintype "power_in"))
      (node (ref "U4") (pin "3") (pinfunction "GND_3") (pintype "bidirectional"))
      (node (ref "U4") (pin "7") (pinfunction "GND_7") (pintype "bidirectional"))
      (node (ref "U5") (pin "4") (pinfunction "GND_4") (pintype "passive"))
      (node (ref "U6") (pin "2") (pinfunction "GND_2") (pintype "bidirectional"))
      (node (ref "VBUS_OUT_J") (pin "2") (pinfunction "2_2") (pintype "bidirectional"))
      (node (ref "X1") (pin "P$2") (pinfunction "2_P$2") (pintype "passive"))
    )
    (net (code "9") (name "IND_LED") (class "Default")
      (node (ref "R2") (pin "1") (pinfunction "1_1") (pintype "passive"))
      (node (ref "U1") (pin "27") (pinfunction "PB15_27") (pintype "bidirectional"))
    )
    (net (code "10") (name "MCU_3V3") (class "Default")
      (node (ref "C21") (pin "2") (pinfunction "2_2") (pintype "passive"))
      (node (ref "C7") (pin "1") (pinfunction "1_1") (pintype "passive"))
      (node (ref "D4") (pin "2") (pinfunction "C_2") (pintype "passive"))
      (node (ref "FB1") (pin "2") (pinfunction "2_2") (pintype "passive"))
      (node (ref "R11") (pin "2") (pinfunction "2_2") (pintype "passive"))
      (node (ref "R21") (pin "2") (pinfunction "2_2") (pintype "passive"))
      (node (ref "R22") (pin "2") (pinfunction "2_2") (pintype "passive"))
      (node (ref "R39") (pin "2") (pinfunction "2_2") (pintype "passive"))
      (node (ref "SJ2") (pin "2") (pinfunction "2_2") (pintype "passive"))
      (node (ref "U5") (pin "3") (pinfunction "VCC_3") (pintype "power_in"))
      (node (ref "U6") (pin "5") (pinfunction "OUT_5") (pintype "bidirectional"))
    )
    (net (code "11") (name "MCU_INT") (class "Default")
      (node (ref "PIO_J") (pin "1") (pinfunction "1_1") (pintype "passive"))
      (node (ref "R16") (pin "1") (pinfunction "1_1") (pintype "passive"))
      (node (ref "R22") (pin "1") (pinfunction "1_1") (pintype "passive"))
      (node (ref "U1") (pin "16") (pinfunction "PA5_16") (pintype "bidirectional"))
    )
    (net (code "12") (name "MCU_LDO_EN") (class "Default")
      (node (ref "D6") (pin "2") (pinfunction "A_2") (pintype "bidirectional"))
      (node (ref "U1") (pin "21") (pinfunction "PB2_21") (pintype "bidirectional"))
    )
    (net (code "13") (name "MCU_SCL") (class "Default")
      (node (ref "R15") (pin "1") (pinfunction "1_1") (pintype "passive"))
      (node (ref "R21") (pin "1") (pinfunction "1_1") (pintype "passive"))
      (node (ref "U1") (pin "18") (pinfunction "PA7_18") (pintype "bidirectional"))
    )
    (net (code "14") (name "MCU_SDA") (class "Default")
      (node (ref "R11") (pin "1") (pinfunction "1_1") (pintype "passive"))
      (node (ref "R17") (pin "1") (pinfunction "1_1") (pintype "passive"))
      (node (ref "U1") (pin "17") (pinfunction "PA6_17") (pintype "bidirectional"))
    )
    (net (code "15") (name "Net-(C18-Pad1)") (class "Default")
      (node (ref "C18") (pin "1") (pinfunction "1_1") (pintype "passive"))
      (node (ref "Q1") (pin "11") (pinfunction "S1_11") (pintype "bidirectional"))
      (node (ref "Q1") (pin "7") (pinfunction "S1_7") (pintype "bidirectional"))
      (node (ref "Q1") (pin "8") (pinfunction "S1_8") (pintype "bidirectional"))
      (node (ref "Q1") (pin "9") (pinfunction "S1_9") (pintype "bidirectional"))
      (node (ref "R5") (pin "1") (pinfunction "1_1") (pintype "passive"))
      (node (ref "R6") (pin "1") (pinfunction "1_1") (pintype "passive"))
    )
    (net (code "16") (name "Net-(D1-PadA)") (class "Default")
      (node (ref "D1") (pin "A") (pinfunction "A_A") (pintype "passive"))
      (node (ref "R2") (pin "2") (pinfunction "2_2") (pintype "passive"))
    )
    (net (code "17") (name "Net-(D3-PadA)") (class "Default")
      (node (ref "D3") (pin "A") (pinfunction "A_A") (pintype "passive"))
      (node (ref "R24") (pin "2") (pinfunction "2_2") (pintype "passive"))
    )
    (net (code "18") (name "Net-(D5-K)") (class "Default")
      (node (ref "D5") (pin "1") (pinfunction "K_1") (pintype "bidirectional"))
      (node (ref "D6") (pin "1") (pinfunction "K_1") (pintype "bidirectional"))
      (node (ref "D7") (pin "1") (pinfunction "K_1") (pintype "bidirectional"))
      (node (ref "R35") (pin "1") (pinfunction "1_1") (pintype "passive"))
    )
    (net (code "19") (name "Net-(D7-A)") (class "Default")
      (node (ref "D7") (pin "2") (pinfunction "A_2") (pintype "bidirectional"))
      (node (ref "SJ3") (pin "1") (pinfunction "1_1") (pintype "passive"))
    )
    (net (code "20") (name "Net-(Q1-D1)") (class "Default")
      (node (ref "Q1") (pin "2") (pinfunction "D1_2") (pintype "bidirectional"))
      (node (ref "Q1") (pin "3") (pinfunction "D2_3") (pintype "bidirectional"))
    )
    (net (code "21") (name "Net-(Q1-G1)") (class "Default")
      (node (ref "Q1") (pin "1") (pinfunction "G1_1") (pintype "bidirectional"))
      (node (ref "R9") (pin "1") (pinfunction "1_1") (pintype "passive"))
    )
    (net (code "22") (name "Net-(Q1-G2)") (class "Default")
      (node (ref "Q1") (pin "4") (pinfunction "G2_4") (pintype "bidirectional"))
      (node (ref "R10") (pin "1") (pinfunction "1_1") (pintype "passive"))
    )
    (net (code "23") (name "Net-(U1-PF0-OSC_IN)") (class "Default")
      (node (ref "U1") (pin "8") (pinfunction "PF0-OSC_IN_8") (pintype "bidirectional"))
      (node (ref "X1") (pin "P$3") (pinfunction "3_P$3") (pintype "passive"))
    )
    (net (code "24") (name "Net-(U1-PF1-OSC_OUT)") (class "Default")
      (node (ref "U1") (pin "9") (pinfunction "PF1-OSC_OUT_9") (pintype "output"))
      (node (ref "X1") (pin "P$1") (pinfunction "1_P$1") (pintype "passive"))
    )
    (net (code "25") (name "Net-(U1-PF2-NRST)") (class "Default")
      (node (ref "C1") (pin "1") (pinfunction "1_1") (pintype "passive"))
      (node (ref "R") (pin "1") (pinfunction "1_1") (pintype "passive"))
      (node (ref "U1") (pin "10") (pinfunction "PF2-NRST_10") (pintype "bidirectional"))
    )
    (net (code "26") (name "Net-(U2-ALRT{slash}PIO)") (class "Default")
      (node (ref "R16") (pin "2") (pinfunction "2_2") (pintype "passive"))
      (node (ref "U2") (pin "B4") (pinfunction "ALRT/PIO_B4") (pintype "output"))
    )
    (net (code "27") (name "Net-(U2-BATT)") (class "Default")
      (node (ref "C12") (pin "2") (pinfunction "2_2") (pintype "passive"))
      (node (ref "C13") (pin "1") (pinfunction "1_1") (pintype "passive"))
      (node (ref "R12") (pin "1") (pinfunction "1_1") (pintype "passive"))
      (node (ref "U2") (pin "C1") (pinfunction "BATT_C1") (pintype "power_in"))
    )
    (net (code "28") (name "Net-(U2-CHG)") (class "Default")
      (node (ref "C18") (pin "2") (pinfunction "2_2") (pintype "passive"))
      (node (ref "R9") (pin "2") (pinfunction "2_2") (pintype "passive"))
      (node (ref "U2") (pin "C2") (pinfunction "CHG_C2") (pintype "passive"))
    )
    (net (code "29") (name "Net-(U2-CP)") (class "Default")
      (node (ref "C12") (pin "1") (pinfunction "1_1") (pintype "passive"))
      (node (ref "U2") (pin "B1") (pinfunction "CP_B1") (pintype "output"))
    )
    (net (code "30") (name "Net-(U2-CSP)") (class "Default")
      (node (ref "C9") (pin "2") (pinfunction "2_2") (pintype "passive"))
      (node (ref "R6") (pin "2") (pinfunction "2_2") (pintype "passive"))
      (node (ref "U2") (pin "A3") (pinfunction "CSP_A3") (pintype "input"))
    )
    (net (code "31") (name "Net-(U2-DIS)") (class "Default")
      (node (ref "R10") (pin "2") (pinfunction "2_2") (pintype "passive"))
      (node (ref "U2") (pin "C3") (pinfunction "DIS_C3") (pintype "passive"))
    )
    (net (code "32") (name "Net-(U2-PCKP)") (class "Default")
      (node (ref "C14") (pin "1") (pinfunction "1_1") (pintype "passive"))
      (node (ref "R18") (pin "2") (pinfunction "2_2") (pintype "passive"))
      (node (ref "U2") (pin "C4") (pinfunction "PCKP_C4") (pintype "passive"))
    )
    (net (code "33") (name "Net-(U2-PFAIL)") (class "Default")
      (node (ref "R19") (pin "1") (pinfunction "1_1") (pintype "passive"))
      (node (ref "U2") (pin "B2") (pinfunction "PFAIL_B2") (pintype "passive"))
    )
    (net (code "34") (name "Net-(U2-REG)") (class "Default")
      (node (ref "C17") (pin "2") (pinfunction "2_2") (pintype "passive"))
      (node (ref "U2") (pin "A5") (pinfunction "REG_A5") (pintype "power_in"))
    )
    (net (code "35") (name "Net-(U2-SCL)") (class "Default")
      (node (ref "R17") (pin "2") (pinfunction "2_2") (pintype "passive"))
      (node (ref "U2") (pin "B5") (pinfunction "SCL_B5") (pintype "input"))
    )
    (net (code "36") (name "Net-(U2-SDA)") (class "Default")
      (node (ref "R15") (pin "2") (pinfunction "2_2") (pintype "passive"))
      (node (ref "U2") (pin "C5") (pinfunction "SDA_C5") (pintype "bidirectional"))
    )
    (net (code "37") (name "Net-(U2-TH)") (class "Default")
      (node (ref "EXT_TH_J") (pin "1") (pinfunction "1_1") (pintype "passive"))
      (node (ref "R14") (pin "2") (pinfunction "2_2") (pintype "passive"))
      (node (ref "R23") (pin "1") (pinfunction "1_1") (pintype "passive"))
      (node (ref "U2") (pin "A1") (pinfunction "TH_A1") (pintype "passive"))
    )
    (net (code "38") (name "Net-(U2-ZVC{slash}TH2)") (class "Default")
      (node (ref "R13") (pin "2") (pinfunction "2_2") (pintype "passive"))
      (node (ref "R30") (pin "1") (pinfunction "1_1") (pintype "passive"))
      (node (ref "U2") (pin "B3") (pinfunction "ZVC/TH2_B3") (pintype "input"))
    )
    (net (code "39") (name "Net-(U3-IN1+)") (class "Default")
      (node (ref "C16") (pin "2") (pinfunction "2_2") (pintype "passive"))
      (node (ref "R7") (pin "1") (pinfunction "1_1") (pintype "passive"))
      (node (ref "R8") (pin "2") (pinfunction "2_2") (pintype "passive"))
      (node (ref "U3") (pin "3") (pinfunction "IN1+_3") (pintype "input"))
    )
    (net (code "40") (name "Net-(U3-IN1-)") (class "Default")
      (node (ref "C10") (pin "1") (pinfunction "1_1") (pintype "passive"))
      (node (ref "R20") (pin "1") (pinfunction "1_1") (pintype "passive"))
      (node (ref "R4") (pin "1") (pinfunction "1_1") (pintype "passive"))
      (node (ref "U3") (pin "2") (pinfunction "IN1-_2") (pintype "input"))
    )
    (net (code "41") (name "Net-(U3-IN2+)") (class "Default")
      (node (ref "C26") (pin "2") (pinfunction "2_2") (pintype "passive"))
      (node (ref "R31") (pin "1") (pinfunction "1_1") (pintype "passive"))
      (node (ref "R32") (pin "2") (pinfunction "2_2") (pintype "passive"))
      (node (ref "R38") (pin "1") (pinfunction "1_1") (pintype "passive"))
      (node (ref "U3") (pin "5") (pinfunction "IN2+_5") (pintype "input"))
    )
    (net (code "42") (name "Net-(U3-IN2-)") (class "Default")
      (node (ref "C27") (pin "2") (pinfunction "2_2") (pintype "passive"))
      (node (ref "D2") (pin "1") (pinfunction "1_1") (pintype "passive"))
      (node (ref "D2") (pin "2") (pinfunction "2_2") (pintype "passive"))
      (node (ref "R33") (pin "1") (pinfunction "1_1") (pintype "passive"))
      (node (ref "R34") (pin "2") (pinfunction "2_2") (pintype "passive"))
      (node (ref "U3") (pin "6") (pinfunction "IN2-_6") (pintype "input"))
    )
    (net (code "43") (name "Net-(U4-EN)") (class "Default")
      (node (ref "C29") (pin "2") (pinfunction "2_2") (pintype "passive"))
      (node (ref "R28") (pin "2") (pinfunction "2_2") (pintype "passive"))
      (node (ref "R36") (pin "2") (pinfunction "2_2") (pintype "passive"))
      (node (ref "U4") (pin "5") (pinfunction "EN_5") (pintype "bidirectional"))
    )
    (net (code "44") (name "Net-(U5-BLEED)") (class "Default")
      (node (ref "R29") (pin "2") (pinfunction "2_2") (pintype "passive"))
      (node (ref "U5") (pin "5") (pinfunction "BLEED_5") (pintype "output"))
    )
    (net (code "45") (name "Net-(U5-EN)") (class "Default")
      (node (ref "C30") (pin "2") (pinfunction "2_2") (pintype "passive"))
      (node (ref "R37") (pin "2") (pinfunction "2_2") (pintype "passive"))
      (node (ref "U5") (pin "2") (pinfunction "EN_2") (pintype "input"))
    )
    (net (code "46") (name "Net-(U5-SR)") (class "Default")
      (node (ref "C23") (pin "2") (pinfunction "2_2") (pintype "passive"))
      (node (ref "U5") (pin "6") (pinfunction "SR_6") (pintype "passive"))
    )
    (net (code "47") (name "Net-(U6-EN)") (class "Default")
      (node (ref "C28") (pin "2") (pinfunction "2_2") (pintype "passive"))
      (node (ref "R25") (pin "1") (pinfunction "1_1") (pintype "passive"))
      (node (ref "R35") (pin "2") (pinfunction "2_2") (pintype "passive"))
      (node (ref "U6") (pin "3") (pinfunction "EN_3") (pintype "bidirectional"))
    )
    (net (code "48") (name "STATUS_LED") (class "Default")
      (node (ref "R24") (pin "1") (pinfunction "1_1") (pintype "passive"))
      (node (ref "U1") (pin "28") (pinfunction "PA8_28") (pintype "bidirectional"))
    )
    (net (code "49") (name "USART1_RX") (class "Default")
      (node (ref "U$1") (pin "PAD_PD4") (pinfunction "SD4_PAD_PD4") (pintype "bidirectional"))
      (node (ref "U1") (pin "32") (pinfunction "PA10_32") (pintype "bidirectional"))
    )
    (net (code "50") (name "USART1_TX") (class "Default")
      (node (ref "U$1") (pin "PAD_PU4") (pinfunction "SU4_PAD_PU4") (pintype "bidirectional"))
      (node (ref "U1") (pin "29") (pinfunction "PA9_29") (pintype "bidirectional"))
    )
    (net (code "51") (name "USART2_RX") (class "Default")
      (node (ref "U$1") (pin "PAD_PD2") (pinfunction "SD2_PAD_PD2") (pintype "bidirectional"))
      (node (ref "U1") (pin "14") (pinfunction "PA3_14") (pintype "bidirectional"))
    )
    (net (code "52") (name "USART2_TX") (class "Default")
      (node (ref "U$1") (pin "PAD_PU2") (pinfunction "SU2_PAD_PU2") (pintype "bidirectional"))
      (node (ref "U1") (pin "13") (pinfunction "PA2_13") (pintype "bidirectional"))
    )
    (net (code "53") (name "USART3_RX") (class "Default")
      (node (ref "U$1") (pin "PAD_PD3") (pinfunction "SD3_PAD_PD3") (pintype "bidirectional"))
      (node (ref "U1") (pin "23") (pinfunction "PB11_23") (pintype "bidirectional"))
    )
    (net (code "54") (name "USART3_TX") (class "Default")
      (node (ref "U$1") (pin "PAD_PU3") (pinfunction "SU3_PAD_PU3") (pintype "bidirectional"))
      (node (ref "U1") (pin "22") (pinfunction "PB10_22") (pintype "bidirectional"))
    )
    (net (code "55") (name "USART4_RX") (class "Default")
      (node (ref "U$1") (pin "PAD_PD1") (pinfunction "SD1_PAD_PD1") (pintype "bidirectional"))
      (node (ref "U1") (pin "12") (pinfunction "PA1_12") (pintype "bidirectional"))
    )
    (net (code "56") (name "USART4_TX") (class "Default")
      (node (ref "U$1") (pin "PAD_PU1") (pinfunction "SU1_PAD_PU1") (pintype "bidirectional"))
      (node (ref "U1") (pin "11") (pinfunction "PA0_11") (pintype "bidirectional"))
    )
    (net (code "57") (name "USART6_RX") (class "Default")
      (node (ref "U$1") (pin "PAD_PD5") (pinfunction "SD5_PAD_PD5") (pintype "bidirectional"))
      (node (ref "U1") (pin "48") (pinfunction "PB9_48") (pintype "bidirectional"))
    )
    (net (code "58") (name "USART6_TX") (class "Default")
      (node (ref "U$1") (pin "PAD_PU5") (pinfunction "SU5_PAD_PU5") (pintype "bidirectional"))
      (node (ref "U1") (pin "47") (pinfunction "PB8_47") (pintype "bidirectional"))
    )
    (net (code "59") (name "VBAT") (class "Default")
      (node (ref "BAT_J") (pin "1") (pinfunction "1_1") (pintype "passive"))
      (node (ref "BAT_J2") (pin "1") (pinfunction "1_1") (pintype "bidirectional"))
      (node (ref "C24") (pin "2") (pinfunction "2_2") (pintype "passive"))
      (node (ref "C32") (pin "1") (pinfunction "1_1") (pintype "passive"))
      (node (ref "R12") (pin "2") (pinfunction "2_2") (pintype "passive"))
      (node (ref "R23") (pin "2") (pinfunction "2_2") (pintype "passive"))
      (node (ref "R5") (pin "2") (pinfunction "2_2") (pintype "passive"))
      (node (ref "U2") (pin "A4") (pinfunction "CSN_A4") (pintype "input"))
    )
    (net (code "60") (name "VBUS") (class "Default")
      (node (ref "C11") (pin "2") (pinfunction "2_2") (pintype "passive"))
      (node (ref "C19") (pin "1") (pinfunction "1_1") (pintype "passive"))
      (node (ref "C6") (pin "1") (pinfunction "1_1") (pintype "passive"))
      (node (ref "Q1") (pin "10") (pinfunction "S2_10") (pintype "bidirectional"))
      (node (ref "Q1") (pin "12") (pinfunction "S2_12") (pintype "bidirectional"))
      (node (ref "Q1") (pin "5") (pinfunction "S2_5") (pintype "bidirectional"))
      (node (ref "Q1") (pin "6") (pinfunction "S2_6") (pintype "bidirectional"))
      (node (ref "R1") (pin "2") (pinfunction "2_2") (pintype "passive"))
      (node (ref "R18") (pin "1") (pinfunction "1_1") (pintype "passive"))
      (node (ref "R26") (pin "2") (pinfunction "2_2") (pintype "passive"))
      (node (ref "R30") (pin "2") (pinfunction "2_2") (pintype "passive"))
      (node (ref "R31") (pin "2") (pinfunction "2_2") (pintype "passive"))
      (node (ref "R33") (pin "2") (pinfunction "2_2") (pintype "passive"))
      (node (ref "R4") (pin "2") (pinfunction "2_2") (pintype "passive"))
      (node (ref "SJ1") (pin "1") (pinfunction "1_1") (pintype "passive"))
      (node (ref "SJ3") (pin "2") (pinfunction "2_2") (pintype "passive"))
      (node (ref "U4") (pin "6") (pinfunction "IN_6") (pintype "bidirectional"))
      (node (ref "U5") (pin "1") (pinfunction "VIN_1") (pintype "power_in"))
      (node (ref "U5") (pin "9") (pinfunction "VIN_9") (pintype "power_in"))
      (node (ref "U6") (pin "1") (pinfunction "IN_1") (pintype "bidirectional"))
    )
    (net (code "61") (name "VBUS_OUT") (class "Default")
      (node (ref "C20") (pin "1") (pinfunction "1_1") (pintype "passive"))
      (node (ref "R29") (pin "1") (pinfunction "1_1") (pintype "passive"))
      (node (ref "SJ1") (pin "2") (pinfunction "2_2") (pintype "passive"))
      (node (ref "U5") (pin "10") (pinfunction "VOUT_10") (pintype "output"))
      (node (ref "U5") (pin "7") (pinfunction "VOUT_7") (pintype "output"))
      (node (ref "U5") (pin "8") (pinfunction "VOUT_8") (pintype "output"))
      (node (ref "VBUS_OUT_J") (pin "1") (pinfunction "1_1") (pintype "bidirectional"))
    )
    (net (code "62") (name "VBUS_OUT_EN") (class "Default")
      (node (ref "R37") (pin "1") (pinfunction "1_1") (pintype "passive"))
      (node (ref "U1") (pin "15") (pinfunction "PA4_15") (pintype "bidirectional"))
    )
    (net (code "63") (name "VBUS_SENSE") (class "Default")
      (node (ref "C22") (pin "1") (pinfunction "1_1") (pintype "passive"))
      (node (ref "R26") (pin "1") (pinfunction "1_1") (pintype "passive"))
      (node (ref "R27") (pin "2") (pinfunction "2_2") (pintype "passive"))
      (node (ref "U1") (pin "20") (pinfunction "PB1_20") (pintype "bidirectional"))
    )
    (net (code "64") (name "VDDA") (class "Default")
      (node (ref "C2") (pin "1") (pinfunction "1_1") (pintype "passive"))
      (node (ref "C3") (pin "1") (pinfunction "+_1") (pintype "passive"))
      (node (ref "FB1") (pin "1") (pinfunction "1_1") (pintype "passive"))
      (node (ref "U1") (pin "6") (pinfunction "VDD/VDDA_6") (pintype "power_in"))
    )
    (net (code "65") (name "VREF") (class "Default")
      (node (ref "C4") (pin "1") (pinfunction "1_1") (pintype "passive"))
      (node (ref "C5") (pin "1") (pinfunction "+_1") (pintype "passive"))
      (node (ref "U1") (pin "5") (pinfunction "VREF+_5") (pintype "power_in"))
    )
    (net (code "66") (name "V_CHARGER") (class "Default")
      (node (ref "C25") (pin "2") (pinfunction "2_2") (pintype "passive"))
      (node (ref "C31") (pin "2") (pinfunction "2_2") (pintype "passive"))
      (node (ref "C8") (pin "1") (pinfunction "1_1") (pintype "passive"))
      (node (ref "J1") (pin "A4") (pinfunction "VBUS_A4") (pintype "bidirectional"))
      (node (ref "J1") (pin "A9") (pinfunction "VBUS_A9") (pintype "bidirectional"))
      (node (ref "J1") (pin "B4") (pinfunction "VBUS_B4") (pintype "bidirectional"))
      (node (ref "J1") (pin "B9") (pinfunction "VBUS_B9") (pintype "bidirectional"))
      (node (ref "R1") (pin "1") (pinfunction "1_1") (pintype "passive"))
      (node (ref "R7") (pin "2") (pinfunction "2_2") (pintype "passive"))
      (node (ref "U3") (pin "8") (pinfunction "VCC+_8") (pintype "power_in"))
    )
    (net (code "67") (name "unconnected-(J1-CC1-PadA5)") (class "Default")
      (node (ref "J1") (pin "A5") (pinfunction "CC1_A5") (pintype "bidirectional"))
    )
    (net (code "68") (name "unconnected-(J1-CC2-PadB5)") (class "Default")
      (node (ref "J1") (pin "B5") (pinfunction "CC2_B5") (pintype "bidirectional"))
    )
    (net (code "69") (name "unconnected-(J1-D+_1-PadA6)") (class "Default")
      (node (ref "J1") (pin "A6") (pinfunction "D+_1_A6") (pintype "bidirectional"))
    )
    (net (code "70") (name "unconnected-(J1-D+_2-PadB6)") (class "Default")
      (node (ref "J1") (pin "B6") (pinfunction "D+_2_B6") (pintype "bidirectional"))
    )
    (net (code "71") (name "unconnected-(J1-D-_1-PadA7)") (class "Default")
      (node (ref "J1") (pin "A7") (pinfunction "D-_1_A7") (pintype "bidirectional"))
    )
    (net (code "72") (name "unconnected-(J1-D-_2-PadB7)") (class "Default")
      (node (ref "J1") (pin "B7") (pinfunction "D-_2_B7") (pintype "bidirectional"))
    )
    (net (code "73") (name "unconnected-(J1-RX1+-PadB11)") (class "Default")
      (node (ref "J1") (pin "B11") (pinfunction "RX1+_B11") (pintype "bidirectional"))
    )
    (net (code "74") (name "unconnected-(J1-RX1--PadB10)") (class "Default")
      (node (ref "J1") (pin "B10") (pinfunction "RX1-_B10") (pintype "bidirectional"))
    )
    (net (code "75") (name "unconnected-(J1-RX2+-PadA11)") (class "Default")
      (node (ref "J1") (pin "A11") (pinfunction "RX2+_A11") (pintype "bidirectional"))
    )
    (net (code "76") (name "unconnected-(J1-RX2--PadA10)") (class "Default")
      (node (ref "J1") (pin "A10") (pinfunction "RX2-_A10") (pintype "bidirectional"))
    )
    (net (code "77") (name "unconnected-(J1-SBU1-PadA8)") (class "Default")
      (node (ref "J1") (pin "A8") (pinfunction "SBU1_A8") (pintype "bidirectional"))
    )
    (net (code "78") (name "unconnected-(J1-SBU2-PadB8)") (class "Default")
      (node (ref "J1") (pin "B8") (pinfunction "SBU2_B8") (pintype "bidirectional"))
    )
    (net (code "79") (name "unconnected-(J1-TX1+-PadA2)") (class "Default")
      (node (ref "J1") (pin "A2") (pinfunction "TX1+_A2") (pintype "bidirectional"))
    )
    (net (code "80") (name "unconnected-(J1-TX1--PadA3)") (class "Default")
      (node (ref "J1") (pin "A3") (pinfunction "TX1-_A3") (pintype "bidirectional"))
    )
    (net (code "81") (name "unconnected-(J1-TX2+-PadB2)") (class "Default")
      (node (ref "J1") (pin "B2") (pinfunction "TX2+_B2") (pintype "bidirectional"))
    )
    (net (code "82") (name "unconnected-(J1-TX2--PadB3)") (class "Default")
      (node (ref "J1") (pin "B3") (pinfunction "TX2-_B3") (pintype "bidirectional"))
    )
    (net (code "83") (name "unconnected-(U1-PA11_[PA9]-Pad33)") (class "Default")
      (node (ref "U1") (pin "33") (pinfunction "PA11_[PA9]_33") (pintype "bidirectional"))
    )
    (net (code "84") (name "unconnected-(U1-PA12_[PA10]-Pad34)") (class "Default")
      (node (ref "U1") (pin "34") (pinfunction "PA12_[PA10]_34") (pintype "bidirectional"))
    )
    (net (code "85") (name "unconnected-(U1-PA15-Pad37)") (class "Default")
      (node (ref "U1") (pin "37") (pinfunction "PA15_37") (pintype "bidirectional"))
    )
    (net (code "86") (name "unconnected-(U1-PB3-Pad42)") (class "Default")
      (node (ref "U1") (pin "42") (pinfunction "PB3_42") (pintype "bidirectional"))
    )
    (net (code "87") (name "unconnected-(U1-PB4-Pad43)") (class "Default")
      (node (ref "U1") (pin "43") (pinfunction "PB4_43") (pintype "bidirectional"))
    )
    (net (code "88") (name "unconnected-(U1-PB5-Pad44)") (class "Default")
      (node (ref "U1") (pin "44") (pinfunction "PB5_44") (pintype "bidirectional"))
    )
    (net (code "89") (name "unconnected-(U1-PB6-Pad45)") (class "Default")
      (node (ref "U1") (pin "45") (pinfunction "PB6_45") (pintype "bidirectional"))
    )
    (net (code "90") (name "unconnected-(U1-PB7-Pad46)") (class "Default")
      (node (ref "U1") (pin "46") (pinfunction "PB7_46") (pintype "bidirectional"))
    )
    (net (code "91") (name "unconnected-(U1-PB14-Pad26)") (class "Default")
      (node (ref "U1") (pin "26") (pinfunction "PB14_26") (pintype "bidirectional"))
    )
    (net (code "92") (name "unconnected-(U1-PC6-Pad30)") (class "Default")
      (node (ref "U1") (pin "30") (pinfunction "PC6_30") (pintype "bidirectional"))
    )
    (net (code "93") (name "unconnected-(U1-PC7-Pad31)") (class "Default")
      (node (ref "U1") (pin "31") (pinfunction "PC7_31") (pintype "bidirectional"))
    )
    (net (code "94") (name "unconnected-(U1-PC13-Pad1)") (class "Default")
      (node (ref "U1") (pin "1") (pinfunction "PC13_1") (pintype "bidirectional"))
    )
    (net (code "95") (name "unconnected-(U1-PC14-OSC32_IN-Pad2)") (class "Default")
      (node (ref "U1") (pin "2") (pinfunction "PC14-OSC32_IN_2") (pintype "bidirectional"))
    )
    (net (code "96") (name "unconnected-(U1-PC15-OSC32_OUT-Pad3)") (class "Default")
      (node (ref "U1") (pin "3") (pinfunction "PC15-OSC32_OUT_3") (pintype "output"))
    )
    (net (code "97") (name "unconnected-(U1-PD0-Pad38)") (class "Default")
      (node (ref "U1") (pin "38") (pinfunction "PD0_38") (pintype "bidirectional"))
    )
    (net (code "98") (name "unconnected-(U1-PD1-Pad39)") (class "Default")
      (node (ref "U1") (pin "39") (pinfunction "PD1_39") (pintype "bidirectional"))
    )
    (net (code "99") (name "unconnected-(U1-PD2-Pad40)") (class "Default")
      (node (ref "U1") (pin "40") (pinfunction "PD2_40") (pintype "bidirectional"))
    )
    (net (code "100") (name "unconnected-(U1-PD3-Pad41)") (class "Default")
      (node (ref "U1") (pin "41") (pinfunction "PD3_41") (pintype "bidirectional"))
    )
    (net (code "101") (name "unconnected-(U1-VBAT-Pad4)") (class "Default")
      (node (ref "U1") (pin "4") (pinfunction "VBAT_4") (pintype "passive"))
    )
    (net (code "102") (name "unconnected-(U6-BYP-Pad4)") (class "Default")
      (node (ref "U6") (pin "4") (pinfunction "BYP_4") (pintype "bidirectional"))
    )
  )
)
